# SCH_esp_charge.net
KiCad netlist of a schematic drawn in EasyEDA
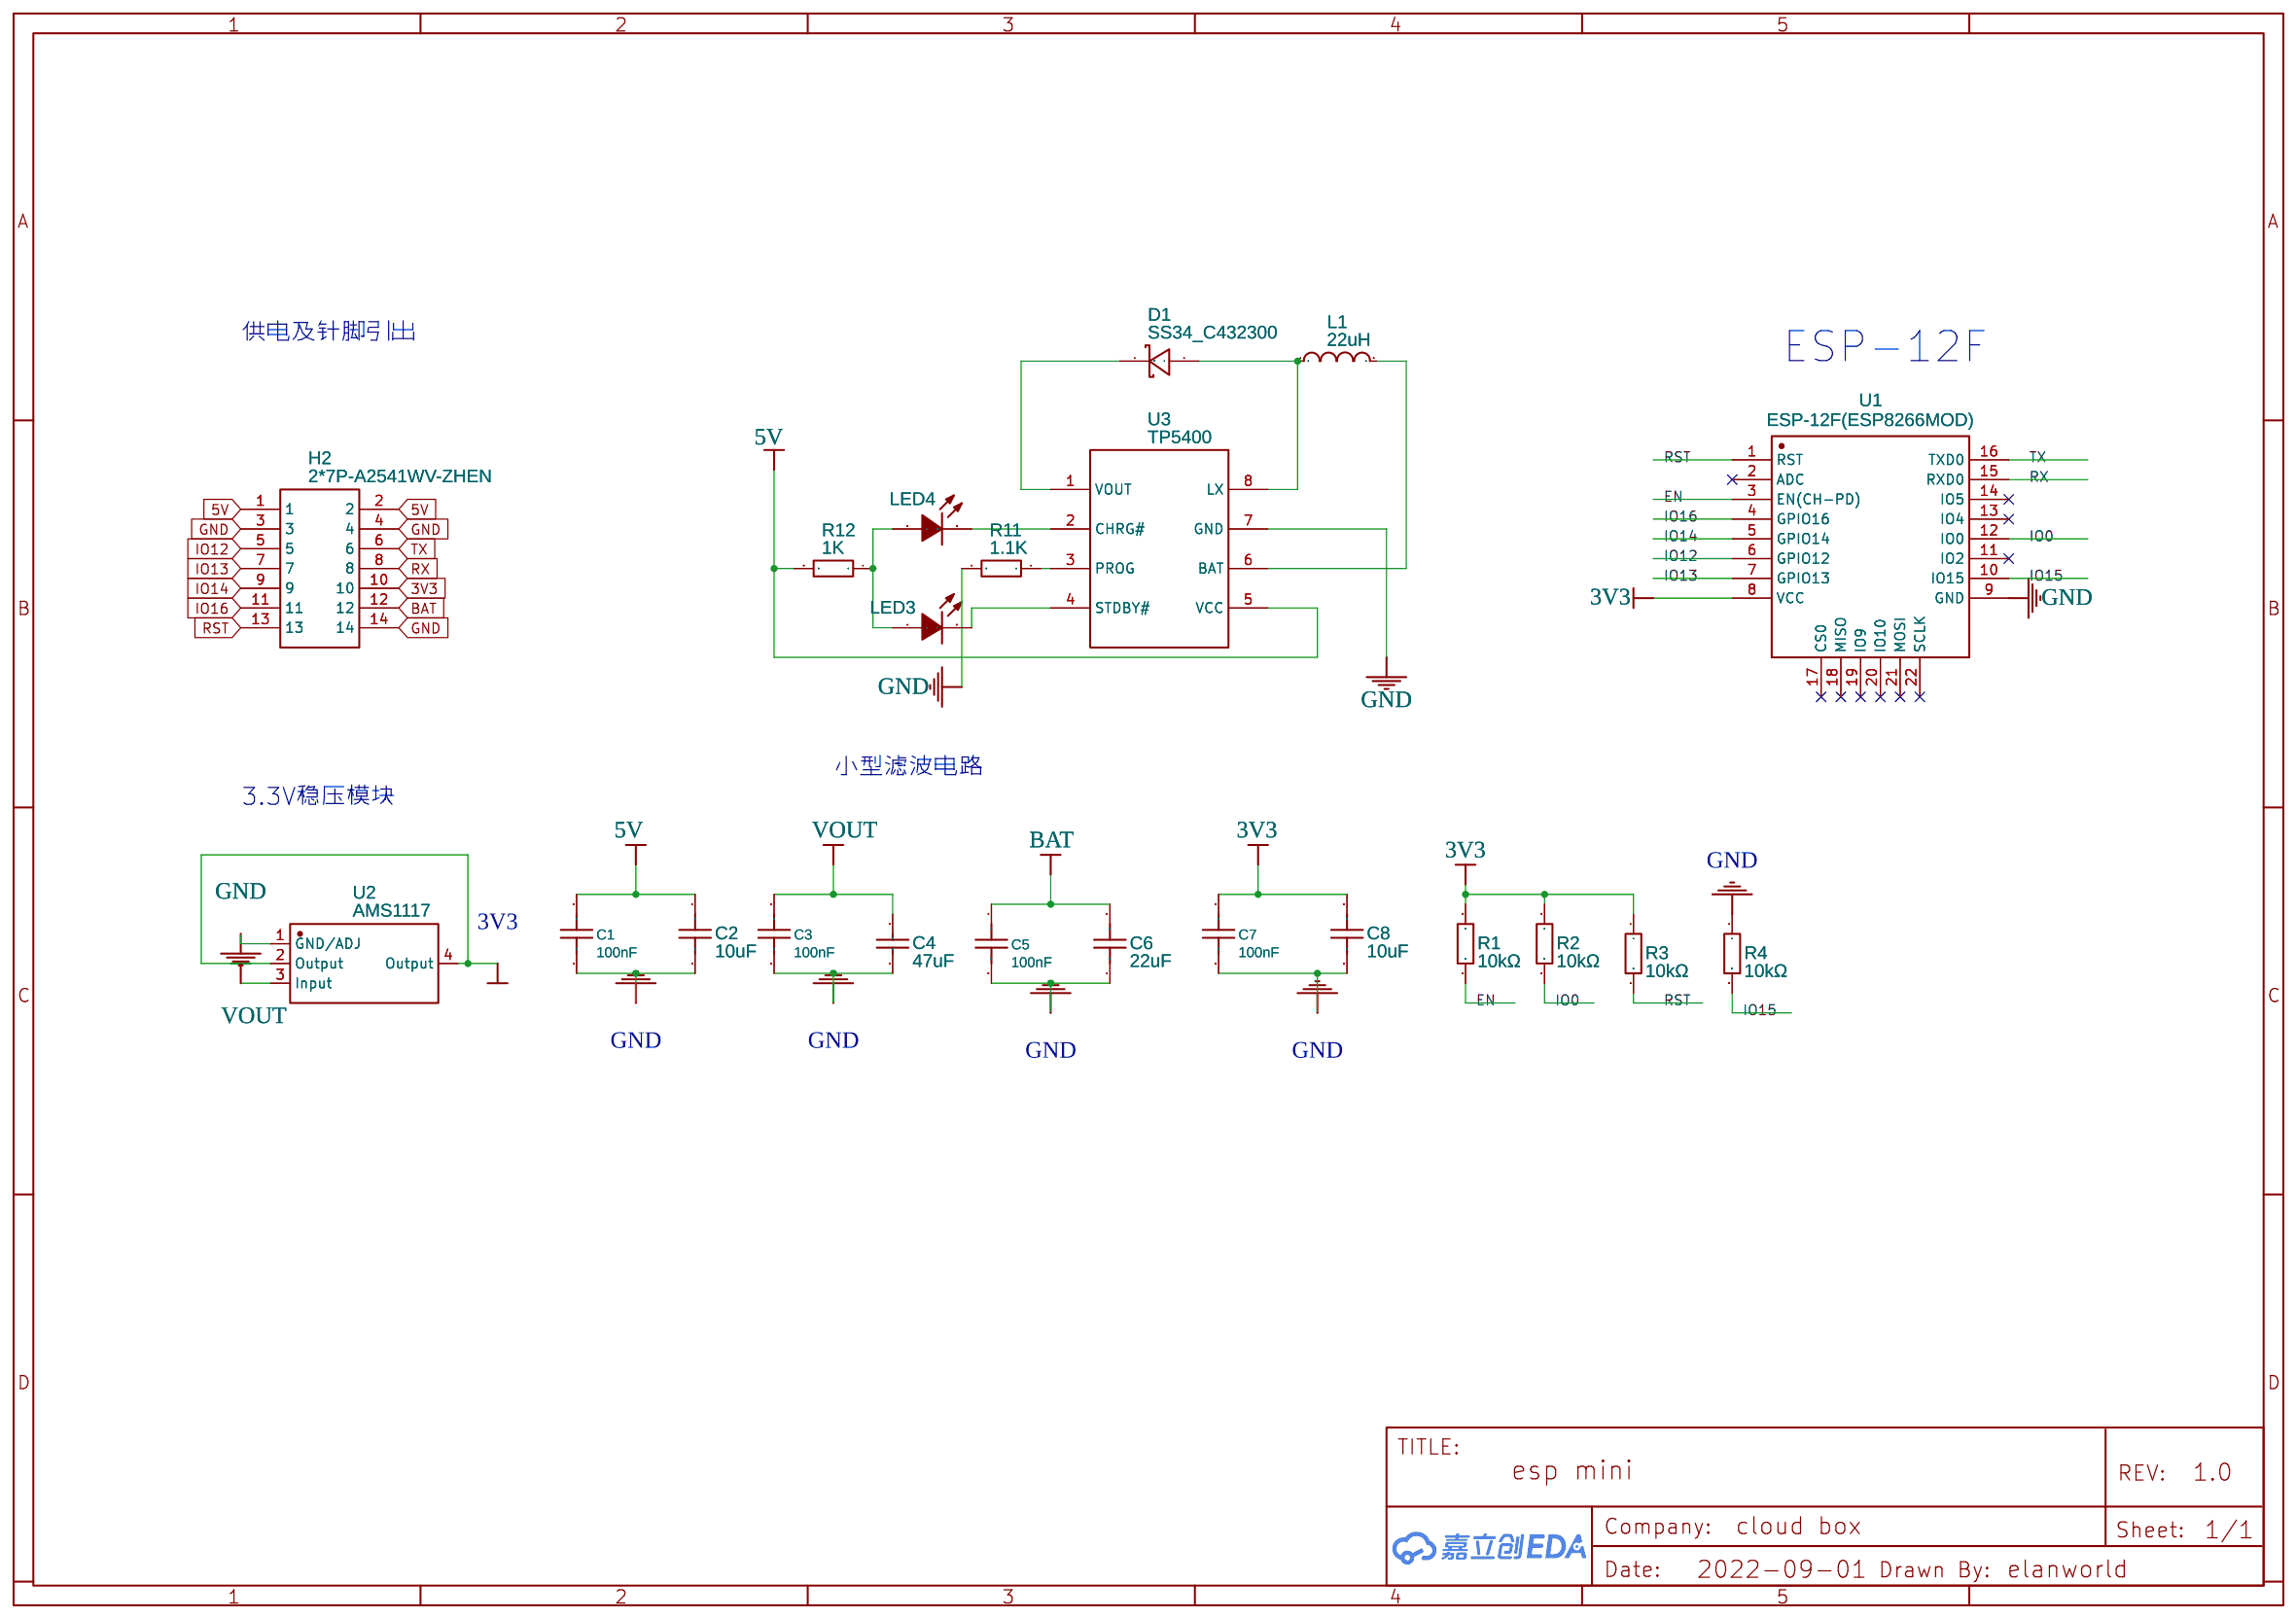
[diagram p0: schematic sheet]

(export (version "E")
  (design (tool "Eeschema 10.0.6"))
  (components
    (comp (ref "C1")
      (value "100nF")
      (fields
        (field (name "BOM_Manufacturer Part") "0805B104K101NT")
        (field (name "BOM_Supplier Part") "C89258")
      )
      (libsource (lib "") (part "0805B104K101NT"))
    )
    (comp (ref "C2")
      (value "10uF")
      (fields
        (field (name "BOM_Manufacturer Part") "C0805X6S106K350NT")
        (field (name "BOM_Supplier Part") "C2844304")
      )
      (libsource (lib "") (part "C0805X6S106K350NT"))
    )
    (comp (ref "C3")
      (value "100nF")
      (fields
        (field (name "BOM_Manufacturer Part") "0805B104K101NT")
        (field (name "BOM_Supplier Part") "C89258")
      )
      (libsource (lib "") (part "0805B104K101NT"))
    )
    (comp (ref "C4")
      (value "47uF")
      (fields
        (field (name "BOM_Manufacturer Part") "0805F476M100NT")
        (field (name "BOM_Supplier Part") "C108658")
      )
      (libsource (lib "") (part "0805F476M100NT"))
    )
    (comp (ref "C5")
      (value "100nF")
      (fields
        (field (name "BOM_Manufacturer Part") "0805B104K101NT")
        (field (name "BOM_Supplier Part") "C89258")
      )
      (libsource (lib "") (part "0805B104K101NT"))
    )
    (comp (ref "C6")
      (value "22uF")
      (fields
        (field (name "BOM_Manufacturer Part") "EMK316ABJ226KL-T")
        (field (name "BOM_Supplier Part") "C319197")
      )
      (libsource (lib "") (part "EMK316ABJ226KL-T"))
    )
    (comp (ref "C7")
      (value "100nF")
      (fields
        (field (name "BOM_Manufacturer Part") "0805B104K101NT")
        (field (name "BOM_Supplier Part") "C89258")
      )
      (libsource (lib "") (part "0805B104K101NT"))
    )
    (comp (ref "C8")
      (value "10uF")
      (fields
        (field (name "BOM_Manufacturer Part") "C0805X6S106K350NT")
        (field (name "BOM_Supplier Part") "C2844304")
      )
      (libsource (lib "") (part "C0805X6S106K350NT"))
    )
    (comp (ref "D1")
      (value "SS34_C432300")
      (fields (field (name "BOM_Manufacturer Part") "SS34") (field (name "BOM_Supplier Part") "C432300"))
      (libsource (lib "") (part "SS34_C432300"))
    )
    (comp (ref "H2")
      (value "2*7P-A2541WV-ZHEN")
      (fields
        (field (name "BOM_Manufacturer Part") "A2541WV-2x7P")
        (field (name "BOM_Supplier Part") "C225522")
      )
      (libsource (lib "") (part "2*7P-A2541WV-ZHEN"))
    )
    (comp (ref "L1")
      (value "22uH")
      (fields
        (field (name "BOM_Manufacturer Part") "TMPC0402HP-100MG-Z02")
        (field (name "BOM_Supplier Part") "C305203")
      )
      (libsource (lib "") (part "TMPC0402HP-100MG-Z02"))
    )
    (comp (ref "LED3")
      (value "D-W080508W1-KS2")
      (fields (field (name "BOM_Supplier Part") "C130115"))
      (libsource (lib "") (part "D-W080508W1-KS2"))
    )
    (comp (ref "LED4")
      (value "D-W080508W1-KS2")
      (fields (field (name "BOM_Supplier Part") "C130115"))
      (libsource (lib "") (part "D-W080508W1-KS2"))
    )
    (comp (ref "R1")
      (value "10kΩ")
      (fields
        (field (name "BOM_Manufacturer Part") "QR0805F10KP05")
        (field (name "BOM_Supplier Part") "C176201")
      )
      (libsource (lib "") (part "QR0805F10KP05"))
    )
    (comp (ref "R2")
      (value "10kΩ")
      (fields
        (field (name "BOM_Manufacturer Part") "QR0805F10KP05")
        (field (name "BOM_Supplier Part") "C176201")
      )
      (libsource (lib "") (part "QR0805F10KP05"))
    )
    (comp (ref "R3")
      (value "10kΩ")
      (fields
        (field (name "BOM_Manufacturer Part") "QR0805F10KP05")
        (field (name "BOM_Supplier Part") "C176201")
      )
      (libsource (lib "") (part "QR0805F10KP05"))
    )
    (comp (ref "R4")
      (value "10kΩ")
      (fields
        (field (name "BOM_Manufacturer Part") "QR0805F10KP05")
        (field (name "BOM_Supplier Part") "C176201")
      )
      (libsource (lib "") (part "QR0805F10KP05"))
    )
    (comp (ref "R11")
      (value "1.1K")
      (fields
        (field (name "BOM_Manufacturer Part") "0805W8F1101T5E")
        (field (name "BOM_Supplier Part") "C17375")
      )
      (libsource (lib "") (part "0805W8F1101T5E"))
    )
    (comp (ref "R12")
      (value "1K")
      (fields
        (field (name "BOM_Manufacturer Part") "0805W8F1101T5E")
        (field (name "BOM_Supplier Part") "C17375")
      )
      (libsource (lib "") (part "0805W8F1101T5E"))
    )
    (comp (ref "U1")
      (value "ESP-12F(ESP8266MOD)")
      (fields (field (name "BOM_Supplier Part") "C82891"))
      (libsource (lib "") (part "ESP-12F(ESP8266MOD)"))
    )
    (comp (ref "U2")
      (value "AMS1117")
      (fields
        (field (name "BOM_Manufacturer Part") "AMS1117-3.3")
        (field (name "BOM_Supplier Part") "C369933")
      )
      (libsource (lib "") (part "AMS1117-3.3_C369933"))
    )
    (comp (ref "U3")
      (value "TP5400")
      (fields (field (name "BOM_Supplier Part") "C24154"))
      (libsource (lib "") (part "TP5400"))
    )
  )
  (nets
    (net (code "1") (name "/EN") (class "Default")
      (node (ref "R1") (pin "2") (pinfunction "2_2") (pintype "unspecified"))
      (node (ref "U1") (pin "3") (pinfunction "EN(CH-PD)_3") (pintype "unspecified"))
    )
    (net (code "2") (name "/IO0") (class "Default")
      (node (ref "R2") (pin "2") (pinfunction "2_2") (pintype "unspecified"))
      (node (ref "U1") (pin "12") (pinfunction "IO0_12") (pintype "unspecified"))
    )
    (net (code "3") (name "/IO15") (class "Default")
      (node (ref "R4") (pin "2") (pinfunction "2_2") (pintype "unspecified"))
      (node (ref "U1") (pin "10") (pinfunction "IO15_10") (pintype "unspecified"))
    )
    (net (code "4") (name "3V3") (class "Default")
      (node (ref "C7") (pin "1") (pinfunction "1_1") (pintype "unspecified"))
      (node (ref "C8") (pin "1") (pinfunction "1_1") (pintype "unspecified"))
      (node (ref "H2") (pin "10") (pinfunction "10_10") (pintype "unspecified"))
      (node (ref "R1") (pin "1") (pinfunction "1_1") (pintype "unspecified"))
      (node (ref "R2") (pin "1") (pinfunction "1_1") (pintype "unspecified"))
      (node (ref "R3") (pin "1") (pinfunction "1_1") (pintype "unspecified"))
      (node (ref "U1") (pin "8") (pinfunction "VCC_8") (pintype "unspecified"))
      (node (ref "U2") (pin "2") (pinfunction "Output_2") (pintype "unspecified"))
      (node (ref "U2") (pin "4") (pinfunction "Output_4") (pintype "unspecified"))
    )
    (net (code "5") (name "5V") (class "Default")
      (node (ref "C1") (pin "1") (pinfunction "1_1") (pintype "unspecified"))
      (node (ref "C2") (pin "1") (pinfunction "1_1") (pintype "unspecified"))
      (node (ref "H2") (pin "1") (pinfunction "1_1") (pintype "unspecified"))
      (node (ref "H2") (pin "2") (pinfunction "2_2") (pintype "unspecified"))
      (node (ref "R12") (pin "2") (pinfunction "2_2") (pintype "input"))
      (node (ref "U3") (pin "5") (pinfunction "VCC_5") (pintype "unspecified"))
    )
    (net (code "6") (name "BAT") (class "Default")
      (node (ref "C5") (pin "1") (pinfunction "1_1") (pintype "unspecified"))
      (node (ref "C6") (pin "2") (pinfunction "2_2") (pintype "unspecified"))
      (node (ref "H2") (pin "12") (pinfunction "12_12") (pintype "unspecified"))
    )
    (net (code "7") (name "GND") (class "Default")
      (node (ref "C1") (pin "2") (pinfunction "2_2") (pintype "unspecified"))
      (node (ref "C2") (pin "2") (pinfunction "2_2") (pintype "unspecified"))
      (node (ref "C3") (pin "2") (pinfunction "2_2") (pintype "unspecified"))
      (node (ref "C4") (pin "1") (pinfunction "1_1") (pintype "input"))
      (node (ref "C5") (pin "2") (pinfunction "2_2") (pintype "unspecified"))
      (node (ref "C6") (pin "1") (pinfunction "1_1") (pintype "unspecified"))
      (node (ref "C7") (pin "2") (pinfunction "2_2") (pintype "unspecified"))
      (node (ref "C8") (pin "2") (pinfunction "2_2") (pintype "unspecified"))
      (node (ref "H2") (pin "14") (pinfunction "14_14") (pintype "unspecified"))
      (node (ref "H2") (pin "3") (pinfunction "3_3") (pintype "unspecified"))
      (node (ref "H2") (pin "4") (pinfunction "4_4") (pintype "unspecified"))
      (node (ref "R11") (pin "2") (pinfunction "2_2") (pintype "input"))
      (node (ref "R4") (pin "1") (pinfunction "1_1") (pintype "unspecified"))
      (node (ref "U1") (pin "9") (pinfunction "GND_9") (pintype "unspecified"))
      (node (ref "U2") (pin "1") (pinfunction "GND/ADJ_1") (pintype "unspecified"))
      (node (ref "U3") (pin "7") (pinfunction "GND_7") (pintype "unspecified"))
    )
    (net (code "8") (name "IO12") (class "Default")
      (node (ref "H2") (pin "5") (pinfunction "5_5") (pintype "unspecified"))
      (node (ref "U1") (pin "6") (pinfunction "GPIO12_6") (pintype "unspecified"))
    )
    (net (code "9") (name "IO13") (class "Default")
      (node (ref "H2") (pin "7") (pinfunction "7_7") (pintype "unspecified"))
      (node (ref "U1") (pin "7") (pinfunction "GPIO13_7") (pintype "unspecified"))
    )
    (net (code "10") (name "IO14") (class "Default")
      (node (ref "H2") (pin "9") (pinfunction "9_9") (pintype "unspecified"))
      (node (ref "U1") (pin "5") (pinfunction "GPIO14_5") (pintype "unspecified"))
    )
    (net (code "11") (name "IO16") (class "Default")
      (node (ref "H2") (pin "11") (pinfunction "11_11") (pintype "unspecified"))
      (node (ref "U1") (pin "4") (pinfunction "GPIO16_4") (pintype "unspecified"))
    )
    (net (code "12") (name "Net-(D1-A)") (class "Default")
      (node (ref "D1") (pin "2") (pinfunction "A_2") (pintype "unspecified"))
      (node (ref "L1") (pin "1") (pinfunction "1_1") (pintype "unspecified"))
      (node (ref "U3") (pin "8") (pinfunction "LX_8") (pintype "unspecified"))
    )
    (net (code "13") (name "Net-(D1-C)") (class "Default")
      (node (ref "D1") (pin "1") (pinfunction "C_1") (pintype "unspecified"))
      (node (ref "U3") (pin "1") (pinfunction "VOUT_1") (pintype "unspecified"))
    )
    (net (code "14") (name "Net-(LED3-A)") (class "Default")
      (node (ref "LED3") (pin "1") (pinfunction "A_1") (pintype "unspecified"))
      (node (ref "LED4") (pin "1") (pinfunction "A_1") (pintype "unspecified"))
      (node (ref "R12") (pin "1") (pinfunction "1_1") (pintype "input"))
    )
    (net (code "15") (name "Net-(LED3-K)") (class "Default")
      (node (ref "LED3") (pin "2") (pinfunction "K_2") (pintype "unspecified"))
      (node (ref "U3") (pin "4") (pinfunction "STDBY#_4") (pintype "unspecified"))
    )
    (net (code "16") (name "Net-(LED4-K)") (class "Default")
      (node (ref "LED4") (pin "2") (pinfunction "K_2") (pintype "unspecified"))
      (node (ref "U3") (pin "2") (pinfunction "CHRG#_2") (pintype "unspecified"))
    )
    (net (code "17") (name "Net-(U3-BAT)") (class "Default")
      (node (ref "L1") (pin "2") (pinfunction "2_2") (pintype "unspecified"))
      (node (ref "U3") (pin "6") (pinfunction "BAT_6") (pintype "unspecified"))
    )
    (net (code "18") (name "Net-(U3-PROG)") (class "Default")
      (node (ref "R11") (pin "1") (pinfunction "1_1") (pintype "input"))
      (node (ref "U3") (pin "3") (pinfunction "PROG_3") (pintype "unspecified"))
    )
    (net (code "19") (name "RST") (class "Default")
      (node (ref "H2") (pin "13") (pinfunction "13_13") (pintype "unspecified"))
      (node (ref "R3") (pin "2") (pinfunction "2_2") (pintype "unspecified"))
      (node (ref "U1") (pin "1") (pinfunction "RST_1") (pintype "unspecified"))
    )
    (net (code "20") (name "RX") (class "Default")
      (node (ref "H2") (pin "8") (pinfunction "8_8") (pintype "unspecified"))
      (node (ref "U1") (pin "15") (pinfunction "RXD0_15") (pintype "unspecified"))
    )
    (net (code "21") (name "TX") (class "Default")
      (node (ref "H2") (pin "6") (pinfunction "6_6") (pintype "unspecified"))
      (node (ref "U1") (pin "16") (pinfunction "TXD0_16") (pintype "unspecified"))
    )
    (net (code "22") (name "VOUT") (class "Default")
      (node (ref "C3") (pin "1") (pinfunction "1_1") (pintype "unspecified"))
      (node (ref "C4") (pin "2") (pinfunction "2_2") (pintype "input"))
      (node (ref "U2") (pin "3") (pinfunction "Input_3") (pintype "unspecified"))
    )
    (net (code "23") (name "unconnected-(U1-ADC-Pad2)") (class "Default")
      (node (ref "U1") (pin "2") (pinfunction "ADC_2") (pintype "unspecified+no_connect"))
    )
    (net (code "24") (name "unconnected-(U1-CS0-Pad17)") (class "Default")
      (node (ref "U1") (pin "17") (pinfunction "CS0_17") (pintype "unspecified+no_connect"))
    )
    (net (code "25") (name "unconnected-(U1-IO2-Pad11)") (class "Default")
      (node (ref "U1") (pin "11") (pinfunction "IO2_11") (pintype "unspecified+no_connect"))
    )
    (net (code "26") (name "unconnected-(U1-IO4-Pad13)") (class "Default")
      (node (ref "U1") (pin "13") (pinfunction "IO4_13") (pintype "unspecified+no_connect"))
    )
    (net (code "27") (name "unconnected-(U1-IO5-Pad14)") (class "Default")
      (node (ref "U1") (pin "14") (pinfunction "IO5_14") (pintype "unspecified+no_connect"))
    )
    (net (code "28") (name "unconnected-(U1-IO9-Pad19)") (class "Default")
      (node (ref "U1") (pin "19") (pinfunction "IO9_19") (pintype "unspecified+no_connect"))
    )
    (net (code "29") (name "unconnected-(U1-IO10-Pad20)") (class "Default")
      (node (ref "U1") (pin "20") (pinfunction "IO10_20") (pintype "unspecified+no_connect"))
    )
    (net (code "30") (name "unconnected-(U1-MISO-Pad18)") (class "Default")
      (node (ref "U1") (pin "18") (pinfunction "MISO_18") (pintype "unspecified+no_connect"))
    )
    (net (code "31") (name "unconnected-(U1-MOSI-Pad21)") (class "Default")
      (node (ref "U1") (pin "21") (pinfunction "MOSI_21") (pintype "unspecified+no_connect"))
    )
    (net (code "32") (name "unconnected-(U1-SCLK-Pad22)") (class "Default")
      (node (ref "U1") (pin "22") (pinfunction "SCLK_22") (pintype "unspecified+no_connect"))
    )
  )
)
